# working.net
KiCad netlist of a schematic drawn in EAGLE
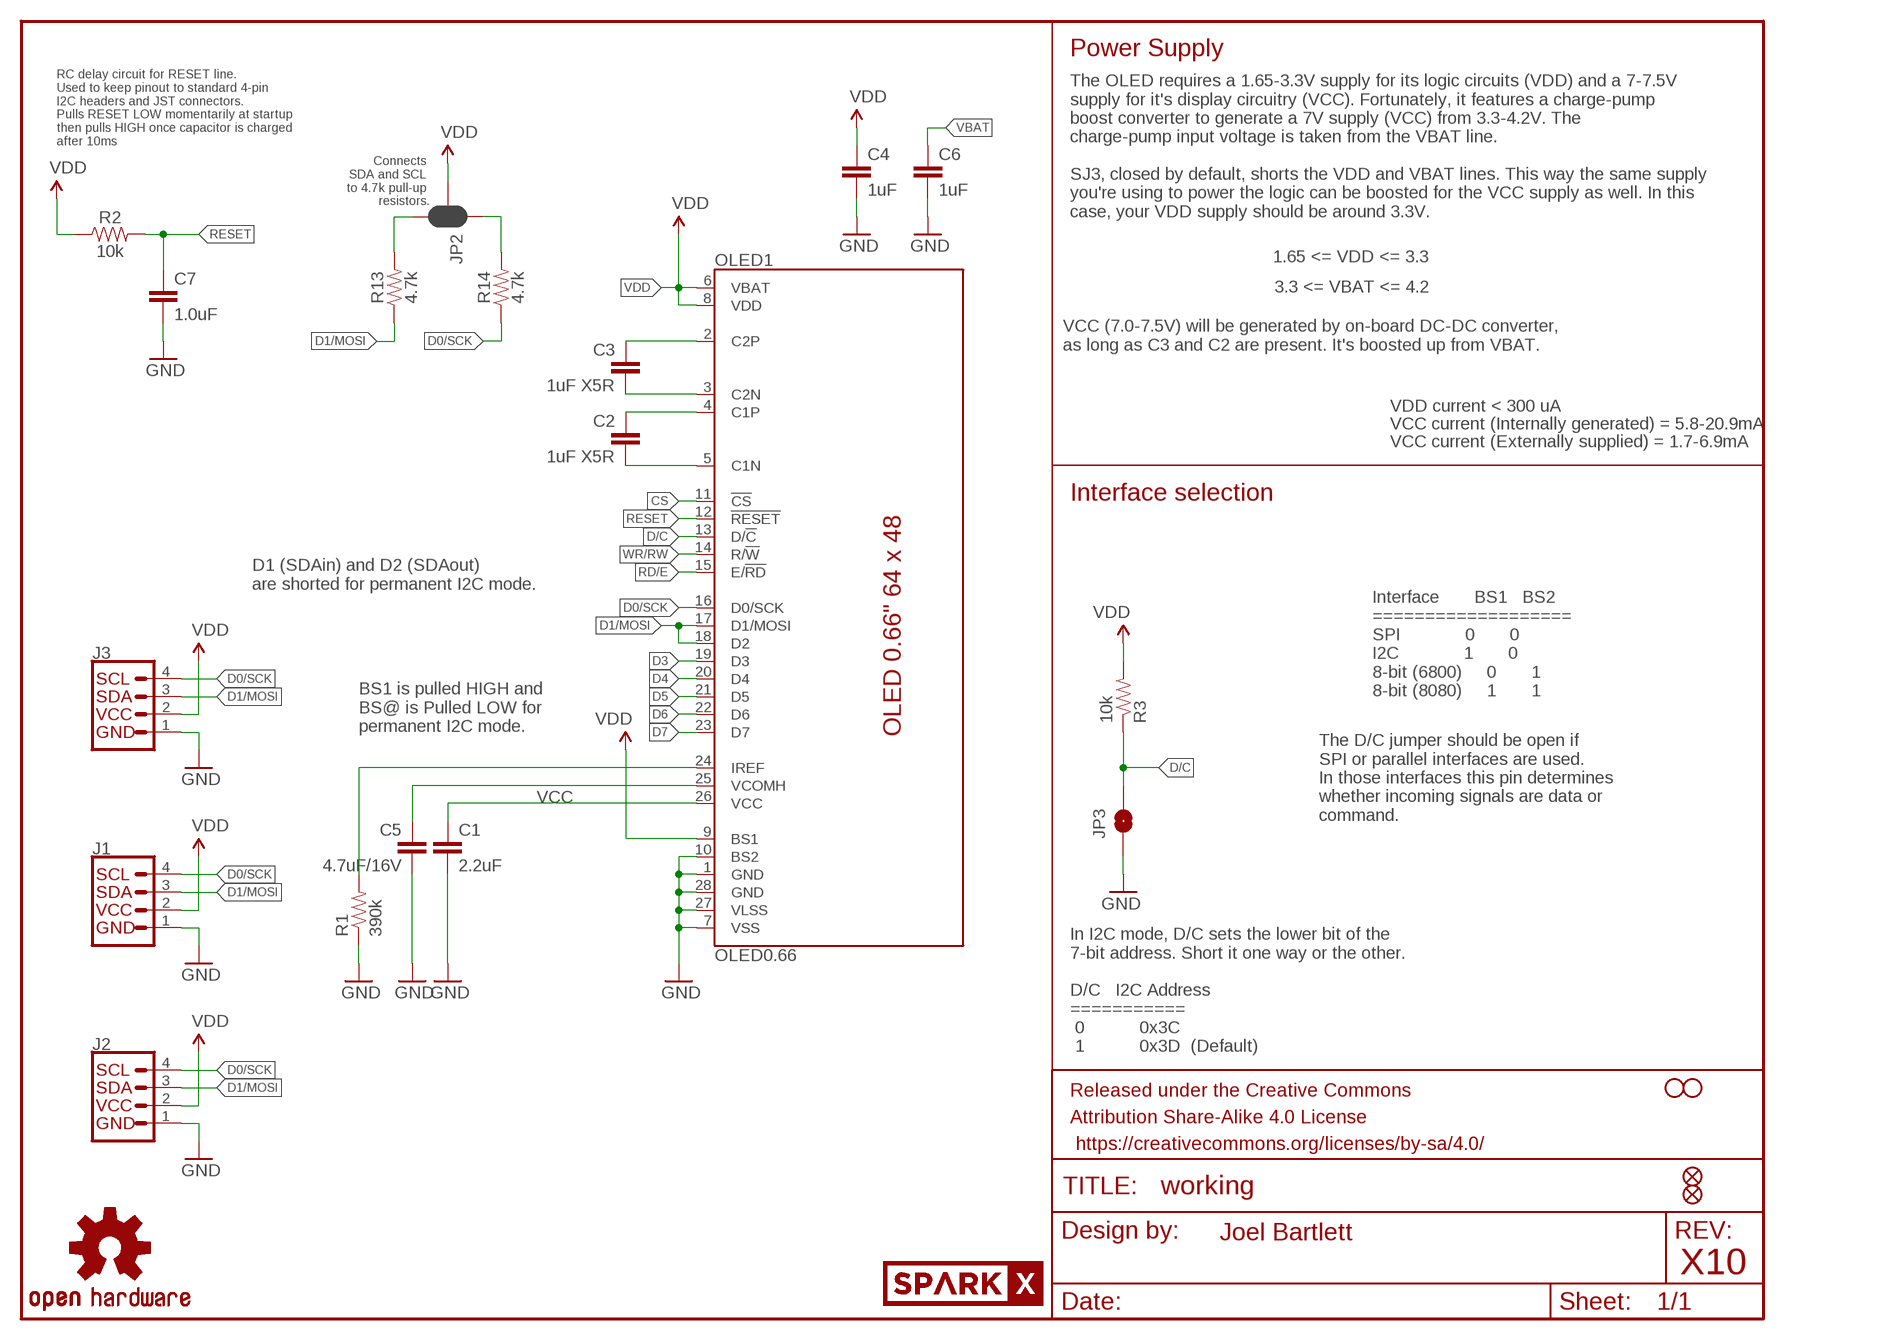
[diagram p0: schematic, sheet 1]

(export (version "E")
  (design (tool "Eeschema 10.0.6"))
  (components
    (comp (ref "C1")
      (value "2.2uF")
      (footprint "eagle-import:0805")
      (libsource (lib "eagle-import") (part "CAP0805"))
    )
    (comp (ref "C2")
      (value "1uF X5R")
      (footprint "eagle-import:0805")
      (libsource (lib "eagle-import") (part "CAP0805"))
    )
    (comp (ref "C3")
      (value "1uF X5R")
      (footprint "eagle-import:0805")
      (libsource (lib "eagle-import") (part "CAP0805"))
    )
    (comp (ref "C4")
      (value "1uF")
      (footprint "eagle-import:0603-CAP")
      (libsource (lib "eagle-import") (part "CAP0603-CAP"))
    )
    (comp (ref "C5")
      (value "4.7uF/16V")
      (footprint "eagle-import:1206")
      (libsource (lib "eagle-import") (part "CAP1206"))
    )
    (comp (ref "C6")
      (value "1uF")
      (footprint "eagle-import:0603-CAP")
      (libsource (lib "eagle-import") (part "CAP0603-CAP"))
    )
    (comp (ref "C7")
      (value "1.0uF")
      (footprint "eagle-import:0603")
      (libsource (lib "eagle-import") (part "1.0UF-0603-16V-10%"))
    )
    (comp (ref "FID1")
      (value "FIDUCIAL1X2")
      (footprint "eagle-import:FIDUCIAL-1X2")
      (libsource (lib "eagle-import") (part "FIDUCIAL1X2"))
    )
    (comp (ref "FID2")
      (value "FIDUCIAL1X2")
      (footprint "eagle-import:FIDUCIAL-1X2")
      (libsource (lib "eagle-import") (part "FIDUCIAL1X2"))
    )
    (comp (ref "FRAME1")
      (value "FRAME-LETTER")
      (footprint "eagle-import:CREATIVE_COMMONS")
      (libsource (lib "eagle-import") (part "FRAME-LETTER"))
    )
    (comp (ref "H1")
      (value "STAND-OFF")
      (footprint "eagle-import:STAND-OFF")
      (libsource (lib "eagle-import") (part "STAND-OFF"))
    )
    (comp (ref "H2")
      (value "STAND-OFF")
      (footprint "eagle-import:STAND-OFF")
      (libsource (lib "eagle-import") (part "STAND-OFF"))
    )
    (comp (ref "J1")
      (value "I2C_STANDARDJS-1MM")
      (footprint "eagle-import:1X04_1MM_RA")
      (libsource (lib "eagle-import") (part "I2C_STANDARDJS-1MM"))
    )
    (comp (ref "J2")
      (value "I2C_STANDARDJS-1MM")
      (footprint "eagle-import:1X04_1MM_RA")
      (libsource (lib "eagle-import") (part "I2C_STANDARDJS-1MM"))
    )
    (comp (ref "J3")
      (value "I2C_STANDARD_NO_SILK")
      (footprint "eagle-import:1X04_NO_SILK")
      (libsource (lib "eagle-import") (part "I2C_STANDARD_NO_SILK"))
    )
    (comp (ref "JP2")
      (value "JUMPER-SMT_3_2-NC_PASTE_SILK")
      (footprint "eagle-import:SMT-JUMPER_3_2-NC_PASTE_SILK")
      (libsource (lib "eagle-import") (part "JUMPER-SMT_3_2-NC_PASTE_SILK"))
    )
    (comp (ref "JP3")
      (value "JUMPER-SMT_2_NO_SILK")
      (footprint "eagle-import:SMT-JUMPER_2_NO_SILK")
      (libsource (lib "eagle-import") (part "JUMPER-SMT_2_NO_SILK"))
    )
    (comp (ref "LOGO3")
      (value "OSHW-LOGOS")
      (footprint "eagle-import:OSHW-LOGO-S")
      (libsource (lib "eagle-import") (part "OSHW-LOGOS"))
    )
    (comp (ref "OLED1")
      (value "OLED0.66")
      (footprint "eagle-import:OLED-0.66-64X48")
      (libsource (lib "eagle-import") (part "OLED0.66"))
    )
    (comp (ref "R1")
      (value "390k")
      (footprint "eagle-import:0603-RES")
      (libsource (lib "eagle-import") (part "RESISTOR0603-RES"))
    )
    (comp (ref "R2")
      (value "10k")
      (footprint "eagle-import:0603")
      (libsource (lib "eagle-import") (part "10KOHM-0603-1/10W-1%"))
    )
    (comp (ref "R3")
      (value "10k")
      (footprint "eagle-import:0603-RES")
      (libsource (lib "eagle-import") (part "RESISTOR0603-RES"))
    )
    (comp (ref "R13")
      (value "4.7k")
      (footprint "eagle-import:0603")
      (libsource (lib "eagle-import") (part "4.7KOHM-0603-1/10W-1%"))
    )
    (comp (ref "R14")
      (value "4.7k")
      (footprint "eagle-import:0603")
      (libsource (lib "eagle-import") (part "4.7KOHM-0603-1/10W-1%"))
    )
    (comp (ref "U$1")
      (value "SPARKX-LOGO4")
      (footprint "eagle-import:SPARKX-MEDIUM")
      (libsource (lib "eagle-import") (part "SPARKX-LOGO4"))
    )
    (comp (ref "U$3")
      (value "SPARKX-LOGO2")
      (footprint "eagle-import:SPARKX-TINY")
      (libsource (lib "eagle-import") (part "SPARKX-LOGO2"))
    )
  )
  (nets
    (net (code "1") (name "/VCC") (class "Default")
      (node (ref "C1") (pin "1") (pinfunction "1_1") (pintype "passive"))
      (node (ref "OLED1") (pin "26") (pinfunction "VCC_26") (pintype "bidirectional"))
    )
    (net (code "2") (name "CS") (class "Default")
      (node (ref "OLED1") (pin "11") (pinfunction "~{CS}_11") (pintype "bidirectional"))
    )
    (net (code "3") (name "D0{slash}SCK") (class "Default")
      (node (ref "J1") (pin "4") (pinfunction "SCL_4") (pintype "passive"))
      (node (ref "J2") (pin "4") (pinfunction "SCL_4") (pintype "passive"))
      (node (ref "J3") (pin "4") (pinfunction "SCL_4") (pintype "passive"))
      (node (ref "OLED1") (pin "16") (pinfunction "D0/SCK_16") (pintype "bidirectional"))
      (node (ref "R14") (pin "1") (pinfunction "1_1") (pintype "passive"))
    )
    (net (code "4") (name "D1{slash}MOSI") (class "Default")
      (node (ref "J1") (pin "3") (pinfunction "SDA_3") (pintype "passive"))
      (node (ref "J2") (pin "3") (pinfunction "SDA_3") (pintype "passive"))
      (node (ref "J3") (pin "3") (pinfunction "SDA_3") (pintype "passive"))
      (node (ref "OLED1") (pin "17") (pinfunction "D1/MOSI_17") (pintype "bidirectional"))
      (node (ref "OLED1") (pin "18") (pinfunction "D2_18") (pintype "bidirectional"))
      (node (ref "R13") (pin "1") (pinfunction "1_1") (pintype "passive"))
    )
    (net (code "5") (name "D3") (class "Default")
      (node (ref "OLED1") (pin "19") (pinfunction "D3_19") (pintype "bidirectional"))
    )
    (net (code "6") (name "D4") (class "Default")
      (node (ref "OLED1") (pin "20") (pinfunction "D4_20") (pintype "bidirectional"))
    )
    (net (code "7") (name "D5") (class "Default")
      (node (ref "OLED1") (pin "21") (pinfunction "D5_21") (pintype "bidirectional"))
    )
    (net (code "8") (name "D6") (class "Default")
      (node (ref "OLED1") (pin "22") (pinfunction "D6_22") (pintype "bidirectional"))
    )
    (net (code "9") (name "D7") (class "Default")
      (node (ref "OLED1") (pin "23") (pinfunction "D7_23") (pintype "bidirectional"))
    )
    (net (code "10") (name "D{slash}C") (class "Default")
      (node (ref "JP3") (pin "2") (pinfunction "2_2") (pintype "passive"))
      (node (ref "OLED1") (pin "13") (pinfunction "D/~{C}_13") (pintype "bidirectional"))
      (node (ref "R3") (pin "1") (pinfunction "1_1") (pintype "passive"))
    )
    (net (code "11") (name "GND") (class "Default")
      (node (ref "C1") (pin "2") (pinfunction "2_2") (pintype "passive"))
      (node (ref "C4") (pin "2") (pinfunction "2_2") (pintype "passive"))
      (node (ref "C5") (pin "2") (pinfunction "2_2") (pintype "passive"))
      (node (ref "C6") (pin "2") (pinfunction "2_2") (pintype "passive"))
      (node (ref "C7") (pin "2") (pinfunction "2_2") (pintype "passive"))
      (node (ref "J1") (pin "1") (pinfunction "GND_1") (pintype "power_in"))
      (node (ref "J2") (pin "1") (pinfunction "GND_1") (pintype "power_in"))
      (node (ref "J3") (pin "1") (pinfunction "GND_1") (pintype "power_in"))
      (node (ref "JP3") (pin "1") (pinfunction "1_1") (pintype "passive"))
      (node (ref "OLED1") (pin "1") (pinfunction "GND_1") (pintype "bidirectional"))
      (node (ref "OLED1") (pin "10") (pinfunction "BS2_10") (pintype "bidirectional"))
      (node (ref "OLED1") (pin "27") (pinfunction "VLSS_27") (pintype "bidirectional"))
      (node (ref "OLED1") (pin "28") (pinfunction "GND_28") (pintype "bidirectional"))
      (node (ref "OLED1") (pin "7") (pinfunction "VSS_7") (pintype "bidirectional"))
      (node (ref "R1") (pin "1") (pinfunction "1_1") (pintype "passive"))
    )
    (net (code "12") (name "Net-(JP2-Pad1)") (class "Default")
      (node (ref "JP2") (pin "1") (pinfunction "1_1") (pintype "passive"))
      (node (ref "R14") (pin "2") (pinfunction "2_2") (pintype "passive"))
    )
    (net (code "13") (name "Net-(JP2-Pad3)") (class "Default")
      (node (ref "JP2") (pin "3") (pinfunction "3_3") (pintype "passive"))
      (node (ref "R13") (pin "2") (pinfunction "2_2") (pintype "passive"))
    )
    (net (code "14") (name "Net-(OLED1-C1N)") (class "Default")
      (node (ref "C2") (pin "2") (pinfunction "2_2") (pintype "passive"))
      (node (ref "OLED1") (pin "5") (pinfunction "C1N_5") (pintype "bidirectional"))
    )
    (net (code "15") (name "Net-(OLED1-C1P)") (class "Default")
      (node (ref "C2") (pin "1") (pinfunction "1_1") (pintype "passive"))
      (node (ref "OLED1") (pin "4") (pinfunction "C1P_4") (pintype "bidirectional"))
    )
    (net (code "16") (name "Net-(OLED1-C2N)") (class "Default")
      (node (ref "C3") (pin "2") (pinfunction "2_2") (pintype "passive"))
      (node (ref "OLED1") (pin "3") (pinfunction "C2N_3") (pintype "bidirectional"))
    )
    (net (code "17") (name "Net-(OLED1-C2P)") (class "Default")
      (node (ref "C3") (pin "1") (pinfunction "1_1") (pintype "passive"))
      (node (ref "OLED1") (pin "2") (pinfunction "C2P_2") (pintype "bidirectional"))
    )
    (net (code "18") (name "Net-(OLED1-IREF)") (class "Default")
      (node (ref "OLED1") (pin "24") (pinfunction "IREF_24") (pintype "bidirectional"))
      (node (ref "R1") (pin "2") (pinfunction "2_2") (pintype "passive"))
    )
    (net (code "19") (name "Net-(OLED1-VCOMH)") (class "Default")
      (node (ref "C5") (pin "1") (pinfunction "1_1") (pintype "passive"))
      (node (ref "OLED1") (pin "25") (pinfunction "VCOMH_25") (pintype "bidirectional"))
    )
    (net (code "20") (name "RD{slash}E") (class "Default")
      (node (ref "OLED1") (pin "15") (pinfunction "E/~{RD}_15") (pintype "bidirectional"))
    )
    (net (code "21") (name "RESET") (class "Default")
      (node (ref "C7") (pin "1") (pinfunction "1_1") (pintype "passive"))
      (node (ref "OLED1") (pin "12") (pinfunction "~{RESET}_12") (pintype "bidirectional"))
      (node (ref "R2") (pin "2") (pinfunction "2_2") (pintype "passive"))
    )
    (net (code "22") (name "VBAT") (class "Default")
      (node (ref "C6") (pin "1") (pinfunction "1_1") (pintype "passive"))
    )
    (net (code "23") (name "VDD") (class "Default")
      (node (ref "C4") (pin "1") (pinfunction "1_1") (pintype "passive"))
      (node (ref "J1") (pin "2") (pinfunction "VCC_2") (pintype "power_in"))
      (node (ref "J2") (pin "2") (pinfunction "VCC_2") (pintype "power_in"))
      (node (ref "J3") (pin "2") (pinfunction "VCC_2") (pintype "power_in"))
      (node (ref "JP2") (pin "2") (pinfunction "2_2") (pintype "passive"))
      (node (ref "OLED1") (pin "6") (pinfunction "VBAT_6") (pintype "bidirectional"))
      (node (ref "OLED1") (pin "8") (pinfunction "VDD_8") (pintype "bidirectional"))
      (node (ref "OLED1") (pin "9") (pinfunction "BS1_9") (pintype "bidirectional"))
      (node (ref "R2") (pin "1") (pinfunction "1_1") (pintype "passive"))
      (node (ref "R3") (pin "2") (pinfunction "2_2") (pintype "passive"))
    )
    (net (code "24") (name "WR{slash}RW") (class "Default")
      (node (ref "OLED1") (pin "14") (pinfunction "R/~{W}_14") (pintype "bidirectional"))
    )
  )
)
